# LM2596.net
KiCad netlist of a schematic drawn in Altium Designer
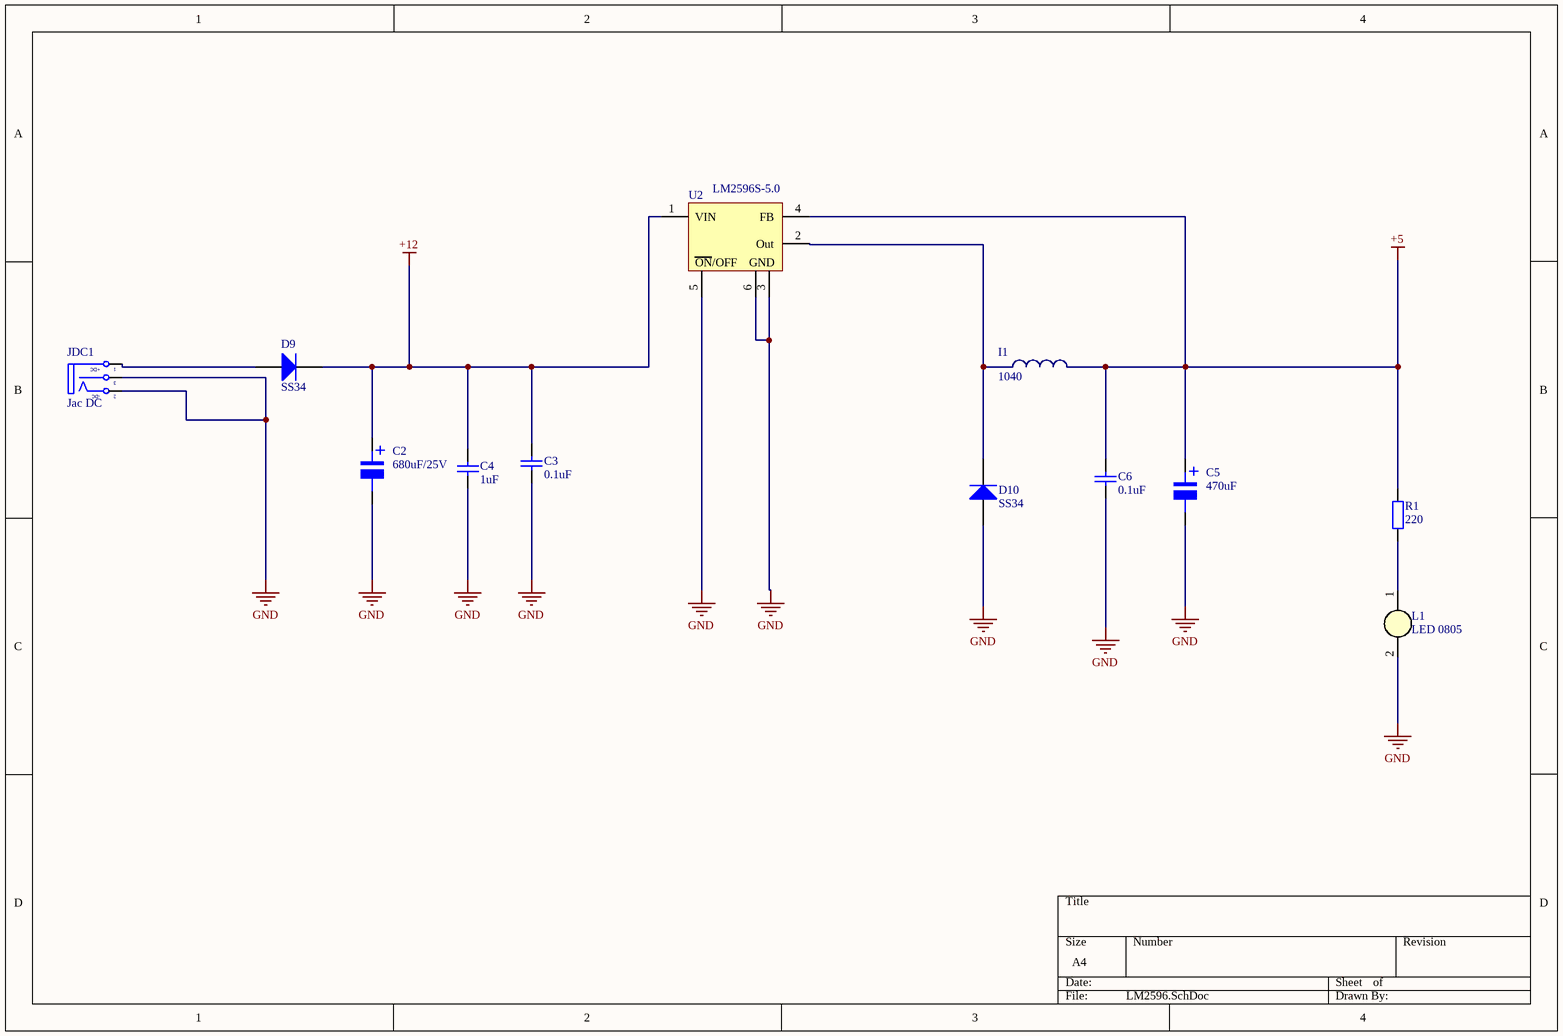
[diagram p0: LM2596.SchDoc]

(export (version "E")
  (design (tool "Eeschema 10.0.6"))
  (components
    (comp (ref "C2")
      (value "680uF/25V")
      (footprint "tu nhom 10 (G)")
      (description "Dán")
      (libsource (lib "Altium_Lib_by_KhueNguyenCreator") (part "Tu Nhom 680uF 16V"))
    )
    (comp (ref "C3")
      (value "0.1uF")
      (footprint "tu 0603")
      (description "Dán")
      (libsource (lib "Altium_Lib_by_KhueNguyenCreator") (part "Tu 0603 104 50V 10%"))
    )
    (comp (ref "C4")
      (value "1uF")
      (footprint "tu 0603")
      (description "Dán")
      (libsource (lib "Altium_Lib_by_KhueNguyenCreator") (part "Tu 0603 105 50V 10%"))
    )
    (comp (ref "C5")
      (value "470uF")
      (footprint "tu nhom 10 (G)")
      (description "Dán")
      (libsource (lib "Altium_Lib_by_KhueNguyenCreator") (part "Tu Nhom 470uF 35V"))
    )
    (comp (ref "C6")
      (value "0.1uF")
      (footprint "tu 0603")
      (description "Dán")
      (libsource (lib "Altium_Lib_by_KhueNguyenCreator") (part "Tu 0603 104 50V 10%"))
    )
    (comp (ref "D9")
      (value "SS34")
      (footprint "DIODE SMA")
      (description "Dán")
      (libsource (lib "Altium_Lib_by_KhueNguyenCreator") (part "Diode SS34 ( 1N5822 )"))
    )
    (comp (ref "D10")
      (value "SS34")
      (footprint "DIODE SMA")
      (description "Dán")
      (libsource (lib "Altium_Lib_by_KhueNguyenCreator") (part "Diode SS34 ( 1N5822 )"))
    )
    (comp (ref "I1")
      (value "1040")
      (footprint "1040")
      (description "Generic Encapsulated Inductor 1040.")
      (libsource (lib "Inductor") (part "1040"))
    )
    (comp (ref "JDC1")
      (value "Jac DC")
      (footprint "DC0")
      (description "Jac DC input")
      (libsource (lib "LIBRARY") (part "DCIN"))
    )
    (comp (ref "L1")
      (value "LED 0805")
      (footprint "LED-0805-Yellow")
      (description "Dán")
      (libsource (lib "Altium_Lib_by_KhueNguyenCreator") (part "LED 0805 Trang"))
    )
    (comp (ref "R1")
      (value "220")
      (footprint "tro smd 0805")
      (description "Dán")
      (libsource (lib "Altium_Lib_by_KhueNguyenCreator") (part "Tro 0805 1% 1k"))
    )
    (comp (ref "U2")
      (value "LM2596S-5.0")
      (footprint "TO-263-5")
      (description "Simple Switcher 3A Step-Down Voltage Regulator")
      (libsource (lib "Integrated_Library1") (part "LM2596S-5.0"))
    )
  )
  (nets
    (net (code "1") (name "+5") (class "Default")
      (node (ref "C5") (pin "1") (pinfunction "1_1") (pintype "passive"))
      (node (ref "C6") (pin "1") (pinfunction "1_1") (pintype "passive"))
      (node (ref "I1") (pin "2") (pinfunction "2_2") (pintype "passive"))
      (node (ref "R1") (pin "2") (pinfunction "2_2") (pintype "passive"))
      (node (ref "U2") (pin "4") (pinfunction "FB_4") (pintype "passive"))
    )
    (net (code "2") (name "+12") (class "Default")
      (node (ref "C2") (pin "1") (pinfunction "1_1") (pintype "passive"))
      (node (ref "C3") (pin "1") (pinfunction "1_1") (pintype "passive"))
      (node (ref "C4") (pin "1") (pinfunction "1_1") (pintype "passive"))
      (node (ref "D9") (pin "2") (pinfunction "K_2") (pintype "passive"))
      (node (ref "U2") (pin "1") (pinfunction "VIN_1") (pintype "passive"))
    )
    (net (code "3") (name "GND") (class "Default")
      (node (ref "C2") (pin "2") (pinfunction "2_2") (pintype "passive"))
      (node (ref "C3") (pin "2") (pinfunction "2_2") (pintype "passive"))
      (node (ref "C4") (pin "2") (pinfunction "2_2") (pintype "passive"))
      (node (ref "C5") (pin "2") (pinfunction "2_2") (pintype "passive"))
      (node (ref "C6") (pin "2") (pinfunction "2_2") (pintype "passive"))
      (node (ref "D10") (pin "1") (pinfunction "A_1") (pintype "passive"))
      (node (ref "JDC1") (pin "2") (pinfunction "TN_2") (pintype "passive"))
      (node (ref "JDC1") (pin "3") (pinfunction "S_3") (pintype "power_in"))
      (node (ref "L1") (pin "2") (pinfunction "K_2") (pintype "passive"))
      (node (ref "U2") (pin "3") (pinfunction "GND_3") (pintype "passive"))
      (node (ref "U2") (pin "5") (pinfunction "~{ON}/OFF_5") (pintype "passive"))
      (node (ref "U2") (pin "6") (pinfunction "PAD_6") (pintype "passive"))
    )
    (net (code "4") (name "Net-(D9-A)") (class "Default")
      (node (ref "D9") (pin "1") (pinfunction "A_1") (pintype "passive"))
      (node (ref "JDC1") (pin "1") (pinfunction "T_1") (pintype "passive"))
    )
    (net (code "5") (name "Net-(D10-K)") (class "Default")
      (node (ref "D10") (pin "2") (pinfunction "K_2") (pintype "passive"))
      (node (ref "I1") (pin "1") (pinfunction "1_1") (pintype "passive"))
      (node (ref "U2") (pin "2") (pinfunction "Out_2") (pintype "passive"))
    )
    (net (code "6") (name "Net-(L1-A)") (class "Default")
      (node (ref "L1") (pin "1") (pinfunction "A_1") (pintype "passive"))
      (node (ref "R1") (pin "1") (pinfunction "1_1") (pintype "passive"))
    )
  )
)
